# power_supply.net
KiCad netlist of a schematic drawn in EAGLE
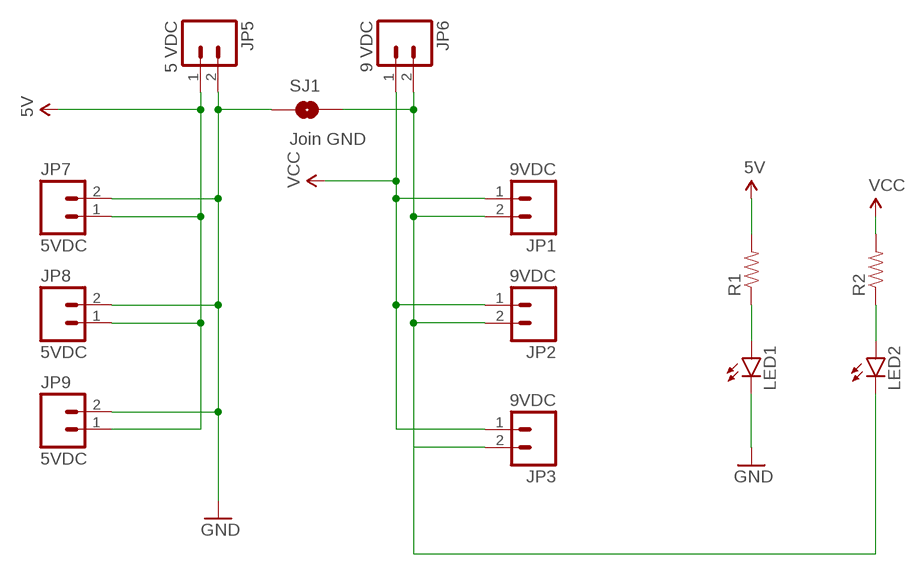
[diagram p0: schematic, sheet 1]

(export (version "E")
  (design (tool "Eeschema 10.0.6"))
  (components
    (comp (ref "JP1")
      (value "9VDC")
      (footprint "eagle-import:1X02")
      (libsource (lib "eagle-import") (part "M02PTH"))
    )
    (comp (ref "JP2")
      (value "9VDC")
      (footprint "eagle-import:1X02")
      (libsource (lib "eagle-import") (part "M02PTH"))
    )
    (comp (ref "JP3")
      (value "9VDC")
      (footprint "eagle-import:1X02")
      (libsource (lib "eagle-import") (part "M02PTH"))
    )
    (comp (ref "JP5")
      (value "5 VDC")
      (footprint "eagle-import:SCREWTERMINAL-5MM-2")
      (libsource (lib "eagle-import") (part "M025MM"))
    )
    (comp (ref "JP6")
      (value "9 VDC")
      (footprint "eagle-import:SCREWTERMINAL-5MM-2")
      (libsource (lib "eagle-import") (part "M025MM"))
    )
    (comp (ref "JP7")
      (value "5VDC")
      (footprint "eagle-import:1X02")
      (libsource (lib "eagle-import") (part "M02PTH"))
    )
    (comp (ref "JP8")
      (value "5VDC")
      (footprint "eagle-import:1X02")
      (libsource (lib "eagle-import") (part "M02PTH"))
    )
    (comp (ref "JP9")
      (value "5VDC")
      (footprint "eagle-import:1X02")
      (libsource (lib "eagle-import") (part "M02PTH"))
    )
    (comp (ref "LED1")
      (value "LED3MM")
      (footprint "eagle-import:LED3MM")
      (libsource (lib "eagle-import") (part "LED3MM"))
    )
    (comp (ref "LED2")
      (value "LED3MM")
      (footprint "eagle-import:LED3MM")
      (libsource (lib "eagle-import") (part "LED3MM"))
    )
    (comp (ref "R1")
      (value "RESISTORAXIAL-0.3")
      (footprint "eagle-import:AXIAL-0.3")
      (libsource (lib "eagle-import") (part "RESISTORAXIAL-0.3"))
    )
    (comp (ref "R2")
      (value "RESISTORAXIAL-0.3")
      (footprint "eagle-import:AXIAL-0.3")
      (libsource (lib "eagle-import") (part "RESISTORAXIAL-0.3"))
    )
    (comp (ref "SJ1")
      (value "Join GND")
      (footprint "eagle-import:SJ_2S-NO")
      (libsource (lib "eagle-import") (part "SOLDERJUMPERNO"))
    )
  )
  (nets
    (net (code "1") (name "5V") (class "Default")
      (node (ref "JP5") (pin "1") (pinfunction "1_1") (pintype "passive"))
      (node (ref "JP7") (pin "1") (pinfunction "1_1") (pintype "passive"))
      (node (ref "JP8") (pin "1") (pinfunction "1_1") (pintype "passive"))
      (node (ref "JP9") (pin "1") (pinfunction "1_1") (pintype "passive"))
      (node (ref "R1") (pin "P$2") (pinfunction "2_P$2") (pintype "passive"))
    )
    (net (code "2") (name "GND") (class "Default")
      (node (ref "JP5") (pin "2") (pinfunction "2_2") (pintype "passive"))
      (node (ref "JP7") (pin "2") (pinfunction "2_2") (pintype "passive"))
      (node (ref "JP8") (pin "2") (pinfunction "2_2") (pintype "passive"))
      (node (ref "JP9") (pin "2") (pinfunction "2_2") (pintype "passive"))
      (node (ref "LED1") (pin "K") (pinfunction "C_K") (pintype "passive"))
      (node (ref "SJ1") (pin "1") (pinfunction "1_1") (pintype "passive"))
    )
    (net (code "3") (name "Net-(LED2-C)") (class "Default")
      (node (ref "JP1") (pin "2") (pinfunction "2_2") (pintype "passive"))
      (node (ref "JP2") (pin "2") (pinfunction "2_2") (pintype "passive"))
      (node (ref "JP3") (pin "2") (pinfunction "2_2") (pintype "passive"))
      (node (ref "JP6") (pin "2") (pinfunction "2_2") (pintype "passive"))
      (node (ref "LED2") (pin "K") (pinfunction "C_K") (pintype "passive"))
      (node (ref "SJ1") (pin "2") (pinfunction "2_2") (pintype "passive"))
    )
    (net (code "4") (name "Net-(R1-1)") (class "Default")
      (node (ref "LED1") (pin "A") (pinfunction "A_A") (pintype "passive"))
      (node (ref "R1") (pin "P$1") (pinfunction "1_P$1") (pintype "passive"))
    )
    (net (code "5") (name "Net-(R2-1)") (class "Default")
      (node (ref "LED2") (pin "A") (pinfunction "A_A") (pintype "passive"))
      (node (ref "R2") (pin "P$1") (pinfunction "1_P$1") (pintype "passive"))
    )
    (net (code "6") (name "VCC") (class "Default")
      (node (ref "JP1") (pin "1") (pinfunction "1_1") (pintype "passive"))
      (node (ref "JP2") (pin "1") (pinfunction "1_1") (pintype "passive"))
      (node (ref "JP3") (pin "1") (pinfunction "1_1") (pintype "passive"))
      (node (ref "JP6") (pin "1") (pinfunction "1_1") (pintype "passive"))
      (node (ref "R2") (pin "P$2") (pinfunction "2_P$2") (pintype "passive"))
    )
  )
)
